# 10_-_COMMUNICATION.net
KiCad netlist of a schematic drawn in Altium Designer
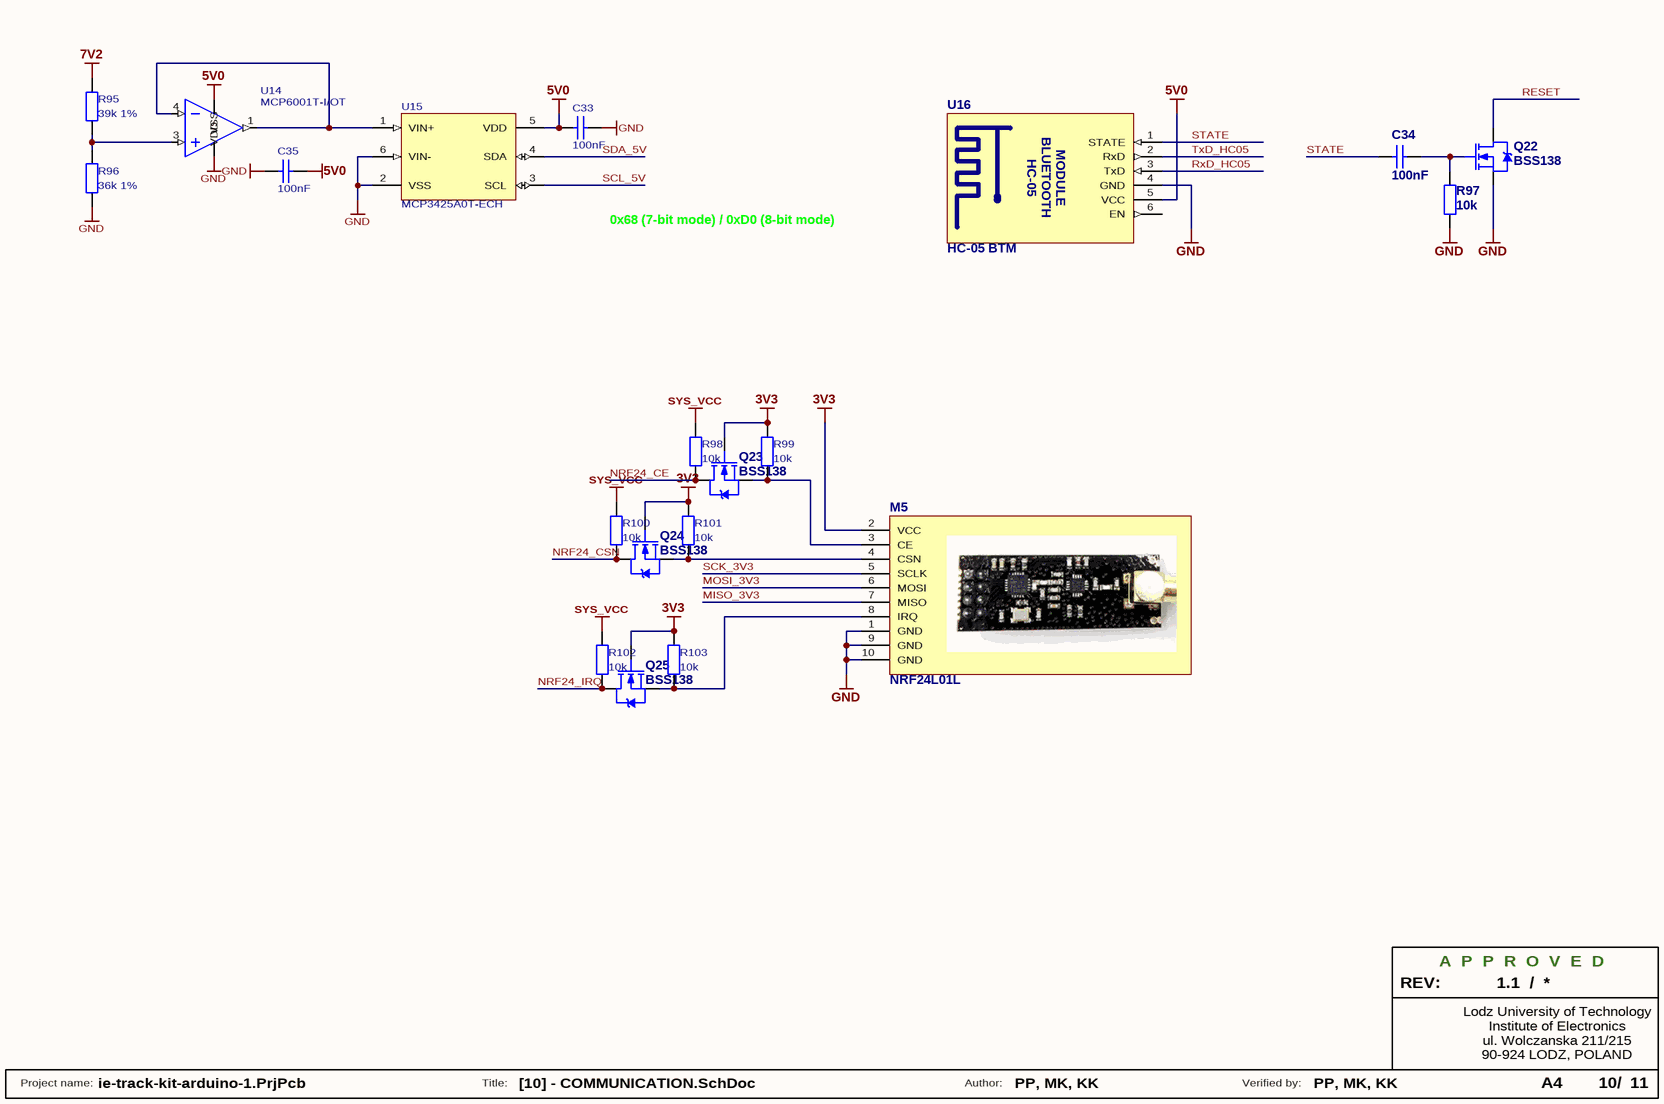
[diagram p0: [10] - COMMUNICATION.SchDoc]

(export (version "E")
  (design (tool "Eeschema 10.0.6"))
  (components
    (comp (ref "C33")
      (value "100nF")
      (footprint "C0805")
      (description "Capacitor")
      (libsource (lib "capacitors") (part "Cap"))
    )
    (comp (ref "C34")
      (value "100nF")
      (footprint "C0805")
      (description "Capacitor")
      (libsource (lib "capacitors") (part "Cap"))
    )
    (comp (ref "C35")
      (value "100nF")
      (footprint "C0805")
      (description "Capacitor")
      (libsource (lib "capacitors") (part "Cap"))
    )
    (comp (ref "M5")
      (value "NRF24L01L")
      (footprint "NRF24L01L")
      (description "Long Range Wireless Module R2 (1.1KM, PA+SMA)")
      (libsource (lib "wireless_modules") (part "NRF24L01L"))
    )
    (comp (ref "Q22")
      (value "BSS138")
      (footprint "SOT-23")
      (description "N-Channel Enhancement Mode Vertical DMOS FET")
      (fields (field (name "PUBLISHER") "Altium Limited"))
      (libsource (lib "transistors_mos") (part "BSS138"))
    )
    (comp (ref "Q23")
      (value "BSS138")
      (footprint "SOT-23")
      (description "N-Channel Enhancement Mode Vertical DMOS FET")
      (fields (field (name "PUBLISHER") "Altium Limited"))
      (libsource (lib "transistors_other") (part "BSS138"))
    )
    (comp (ref "Q24")
      (value "BSS138")
      (footprint "SOT-23")
      (description "N-Channel Enhancement Mode Vertical DMOS FET")
      (fields (field (name "PUBLISHER") "Altium Limited"))
      (libsource (lib "transistors_other") (part "BSS138"))
    )
    (comp (ref "Q25")
      (value "BSS138")
      (footprint "SOT-23")
      (description "N-Channel Enhancement Mode Vertical DMOS FET")
      (fields (field (name "PUBLISHER") "Altium Limited"))
      (libsource (lib "transistors_other") (part "BSS138"))
    )
    (comp (ref "R95")
      (value "39k 1%")
      (footprint "R0805")
      (description "Resistor")
      (libsource (lib "resistors") (part "Res"))
    )
    (comp (ref "R96")
      (value "36k 1%")
      (footprint "R0805")
      (description "Resistor")
      (libsource (lib "resistors") (part "Res"))
    )
    (comp (ref "R97")
      (value "10k")
      (footprint "R0805")
      (description "Resistor")
      (libsource (lib "") (part "Res_1"))
    )
    (comp (ref "R98")
      (value "10k")
      (footprint "R0805")
      (description "Resistor")
      (libsource (lib "resistors") (part "Res"))
    )
    (comp (ref "R99")
      (value "10k")
      (footprint "R0805")
      (description "Resistor")
      (libsource (lib "resistors") (part "Res"))
    )
    (comp (ref "R100")
      (value "10k")
      (footprint "R0805")
      (description "Resistor")
      (libsource (lib "resistors") (part "Res"))
    )
    (comp (ref "R101")
      (value "10k")
      (footprint "R0805")
      (description "Resistor")
      (libsource (lib "resistors") (part "Res"))
    )
    (comp (ref "R102")
      (value "10k")
      (footprint "R0805")
      (description "Resistor")
      (libsource (lib "resistors") (part "Res"))
    )
    (comp (ref "R103")
      (value "10k")
      (footprint "R0805")
      (description "Resistor")
      (libsource (lib "resistors") (part "Res"))
    )
    (comp (ref "U14")
      (value "MCP6001T-I/OT")
      (footprint "SOT-23-5")
      (description "Rail-to-rail, 1MHz, 100uA Op Amp")
      (libsource (lib "opamps") (part "MCP6001T-I/OT"))
    )
    (comp (ref "U15")
      (value "MCP3425A0T-ECH")
      (footprint "SOT-23-6")
      (description "16-Bit Analog-to-Digital Converter with I2C Interface and On-Board Reference")
      (libsource (lib "ad_converters") (part "MCP3425A0T-ECH"))
    )
    (comp (ref "U16")
      (value "HC-05 BTM")
      (footprint "HC-05_H_2")
      (description "HC-05 Bluetooth Module")
      (libsource (lib "wireless_modules") (part "HC-05_BTM"))
    )
  )
  (nets
    (net (code "1") (name "/MISO_3V3") (class "Default")
      (node (ref "M5") (pin "7") (pinfunction "MISO_7") (pintype "passive"))
    )
    (net (code "2") (name "/MOSI_3V3") (class "Default")
      (node (ref "M5") (pin "6") (pinfunction "MOSI_6") (pintype "passive"))
    )
    (net (code "3") (name "/NRF24_CE") (class "Default")
      (node (ref "Q23") (pin "3") (pinfunction "D_3") (pintype "passive"))
      (node (ref "R98") (pin "2") (pinfunction "2_2") (pintype "passive"))
    )
    (net (code "4") (name "/NRF24_CSN") (class "Default")
      (node (ref "Q24") (pin "3") (pinfunction "D_3") (pintype "passive"))
      (node (ref "R100") (pin "2") (pinfunction "2_2") (pintype "passive"))
    )
    (net (code "5") (name "/NRF24_IRQ") (class "Default")
      (node (ref "Q25") (pin "3") (pinfunction "D_3") (pintype "passive"))
      (node (ref "R102") (pin "2") (pinfunction "2_2") (pintype "passive"))
    )
    (net (code "6") (name "/RESET") (class "Default")
      (node (ref "Q22") (pin "3") (pinfunction "D_3") (pintype "passive"))
    )
    (net (code "7") (name "/RxD_HC05") (class "Default")
      (node (ref "U16") (pin "3") (pinfunction "TxD_3") (pintype "input"))
    )
    (net (code "8") (name "/SCK_3V3") (class "Default")
      (node (ref "M5") (pin "5") (pinfunction "SCLK_5") (pintype "passive"))
    )
    (net (code "9") (name "/SCL_5V") (class "Default")
      (node (ref "U15") (pin "3") (pinfunction "SCL_3") (pintype "bidirectional"))
    )
    (net (code "10") (name "/SDA_5V") (class "Default")
      (node (ref "U15") (pin "4") (pinfunction "SDA_4") (pintype "bidirectional"))
    )
    (net (code "11") (name "/STATE") (class "Default")
      (node (ref "C34") (pin "1") (pinfunction "1_1") (pintype "passive"))
      (node (ref "U16") (pin "1") (pinfunction "STATE_1") (pintype "input"))
    )
    (net (code "12") (name "/TxD_HC05") (class "Default")
      (node (ref "U16") (pin "2") (pinfunction "RxD_2") (pintype "output"))
    )
    (net (code "13") (name "3V3") (class "Default")
      (node (ref "M5") (pin "2") (pinfunction "VCC_2") (pintype "passive"))
      (node (ref "Q23") (pin "1") (pinfunction "G_1") (pintype "passive"))
      (node (ref "Q24") (pin "1") (pinfunction "G_1") (pintype "passive"))
      (node (ref "Q25") (pin "1") (pinfunction "G_1") (pintype "passive"))
      (node (ref "R101") (pin "1") (pinfunction "1_1") (pintype "passive"))
      (node (ref "R103") (pin "1") (pinfunction "1_1") (pintype "passive"))
      (node (ref "R99") (pin "1") (pinfunction "1_1") (pintype "passive"))
    )
    (net (code "14") (name "5V0") (class "Default")
      (node (ref "C33") (pin "1") (pinfunction "1_1") (pintype "passive"))
      (node (ref "C35") (pin "1") (pinfunction "1_1") (pintype "passive"))
      (node (ref "U14") (pin "5") (pinfunction "VDD_5") (pintype "power_in"))
      (node (ref "U15") (pin "5") (pinfunction "VDD_5") (pintype "power_in"))
      (node (ref "U16") (pin "5") (pinfunction "VCC_5") (pintype "power_in"))
    )
    (net (code "15") (name "7V2") (class "Default")
      (node (ref "R95") (pin "1") (pinfunction "1_1") (pintype "passive"))
    )
    (net (code "16") (name "GND") (class "Default")
      (node (ref "C33") (pin "2") (pinfunction "2_2") (pintype "passive"))
      (node (ref "C35") (pin "2") (pinfunction "2_2") (pintype "passive"))
      (node (ref "M5") (pin "1") (pinfunction "GND_1") (pintype "passive"))
      (node (ref "M5") (pin "10") (pinfunction "GND_10") (pintype "passive"))
      (node (ref "M5") (pin "9") (pinfunction "GND_9") (pintype "passive"))
      (node (ref "Q22") (pin "2") (pinfunction "S_2") (pintype "passive"))
      (node (ref "R96") (pin "2") (pinfunction "2_2") (pintype "passive"))
      (node (ref "R97") (pin "2") (pinfunction "2_2") (pintype "passive"))
      (node (ref "U14") (pin "2") (pinfunction "VSS_2") (pintype "power_in"))
      (node (ref "U15") (pin "2") (pinfunction "VSS_2") (pintype "power_in"))
      (node (ref "U15") (pin "6") (pinfunction "VIN-_6") (pintype "input"))
      (node (ref "U16") (pin "4") (pinfunction "GND_4") (pintype "power_in"))
    )
    (net (code "17") (name "Net-(M5-CE)") (class "Default")
      (node (ref "M5") (pin "3") (pinfunction "CE_3") (pintype "passive"))
      (node (ref "Q23") (pin "2") (pinfunction "S_2") (pintype "passive"))
      (node (ref "R99") (pin "2") (pinfunction "2_2") (pintype "passive"))
    )
    (net (code "18") (name "Net-(M5-CSN)") (class "Default")
      (node (ref "M5") (pin "4") (pinfunction "CSN_4") (pintype "passive"))
      (node (ref "Q24") (pin "2") (pinfunction "S_2") (pintype "passive"))
      (node (ref "R101") (pin "2") (pinfunction "2_2") (pintype "passive"))
    )
    (net (code "19") (name "Net-(M5-IRQ)") (class "Default")
      (node (ref "M5") (pin "8") (pinfunction "IRQ_8") (pintype "passive"))
      (node (ref "Q25") (pin "2") (pinfunction "S_2") (pintype "passive"))
      (node (ref "R103") (pin "2") (pinfunction "2_2") (pintype "passive"))
    )
    (net (code "20") (name "Net-(Q22-G)") (class "Default")
      (node (ref "C34") (pin "2") (pinfunction "2_2") (pintype "passive"))
      (node (ref "Q22") (pin "1") (pinfunction "G_1") (pintype "passive"))
      (node (ref "R97") (pin "1") (pinfunction "1_1") (pintype "passive"))
    )
    (net (code "21") (name "Net-(U14-IN+)") (class "Default")
      (node (ref "R95") (pin "2") (pinfunction "2_2") (pintype "passive"))
      (node (ref "R96") (pin "1") (pinfunction "1_1") (pintype "passive"))
      (node (ref "U14") (pin "3") (pinfunction "IN+_3") (pintype "input"))
    )
    (net (code "22") (name "Net-(U14-IN-)") (class "Default")
      (node (ref "U14") (pin "1") (pinfunction "OUT_1") (pintype "output"))
      (node (ref "U14") (pin "4") (pinfunction "IN-_4") (pintype "input"))
      (node (ref "U15") (pin "1") (pinfunction "VIN+_1") (pintype "input"))
    )
    (net (code "23") (name "SYS_VCC") (class "Default")
      (node (ref "R100") (pin "1") (pinfunction "1_1") (pintype "passive"))
      (node (ref "R102") (pin "1") (pinfunction "1_1") (pintype "passive"))
      (node (ref "R98") (pin "1") (pinfunction "1_1") (pintype "passive"))
    )
    (net (code "24") (name "unconnected-(U16-EN-Pad6)") (class "Default")
      (node (ref "U16") (pin "6") (pinfunction "EN_6") (pintype "output"))
    )
  )
)
